# 105358-3SC001-01-B_CPU_BRD.net
KiCad netlist of a schematic drawn in Altium Designer
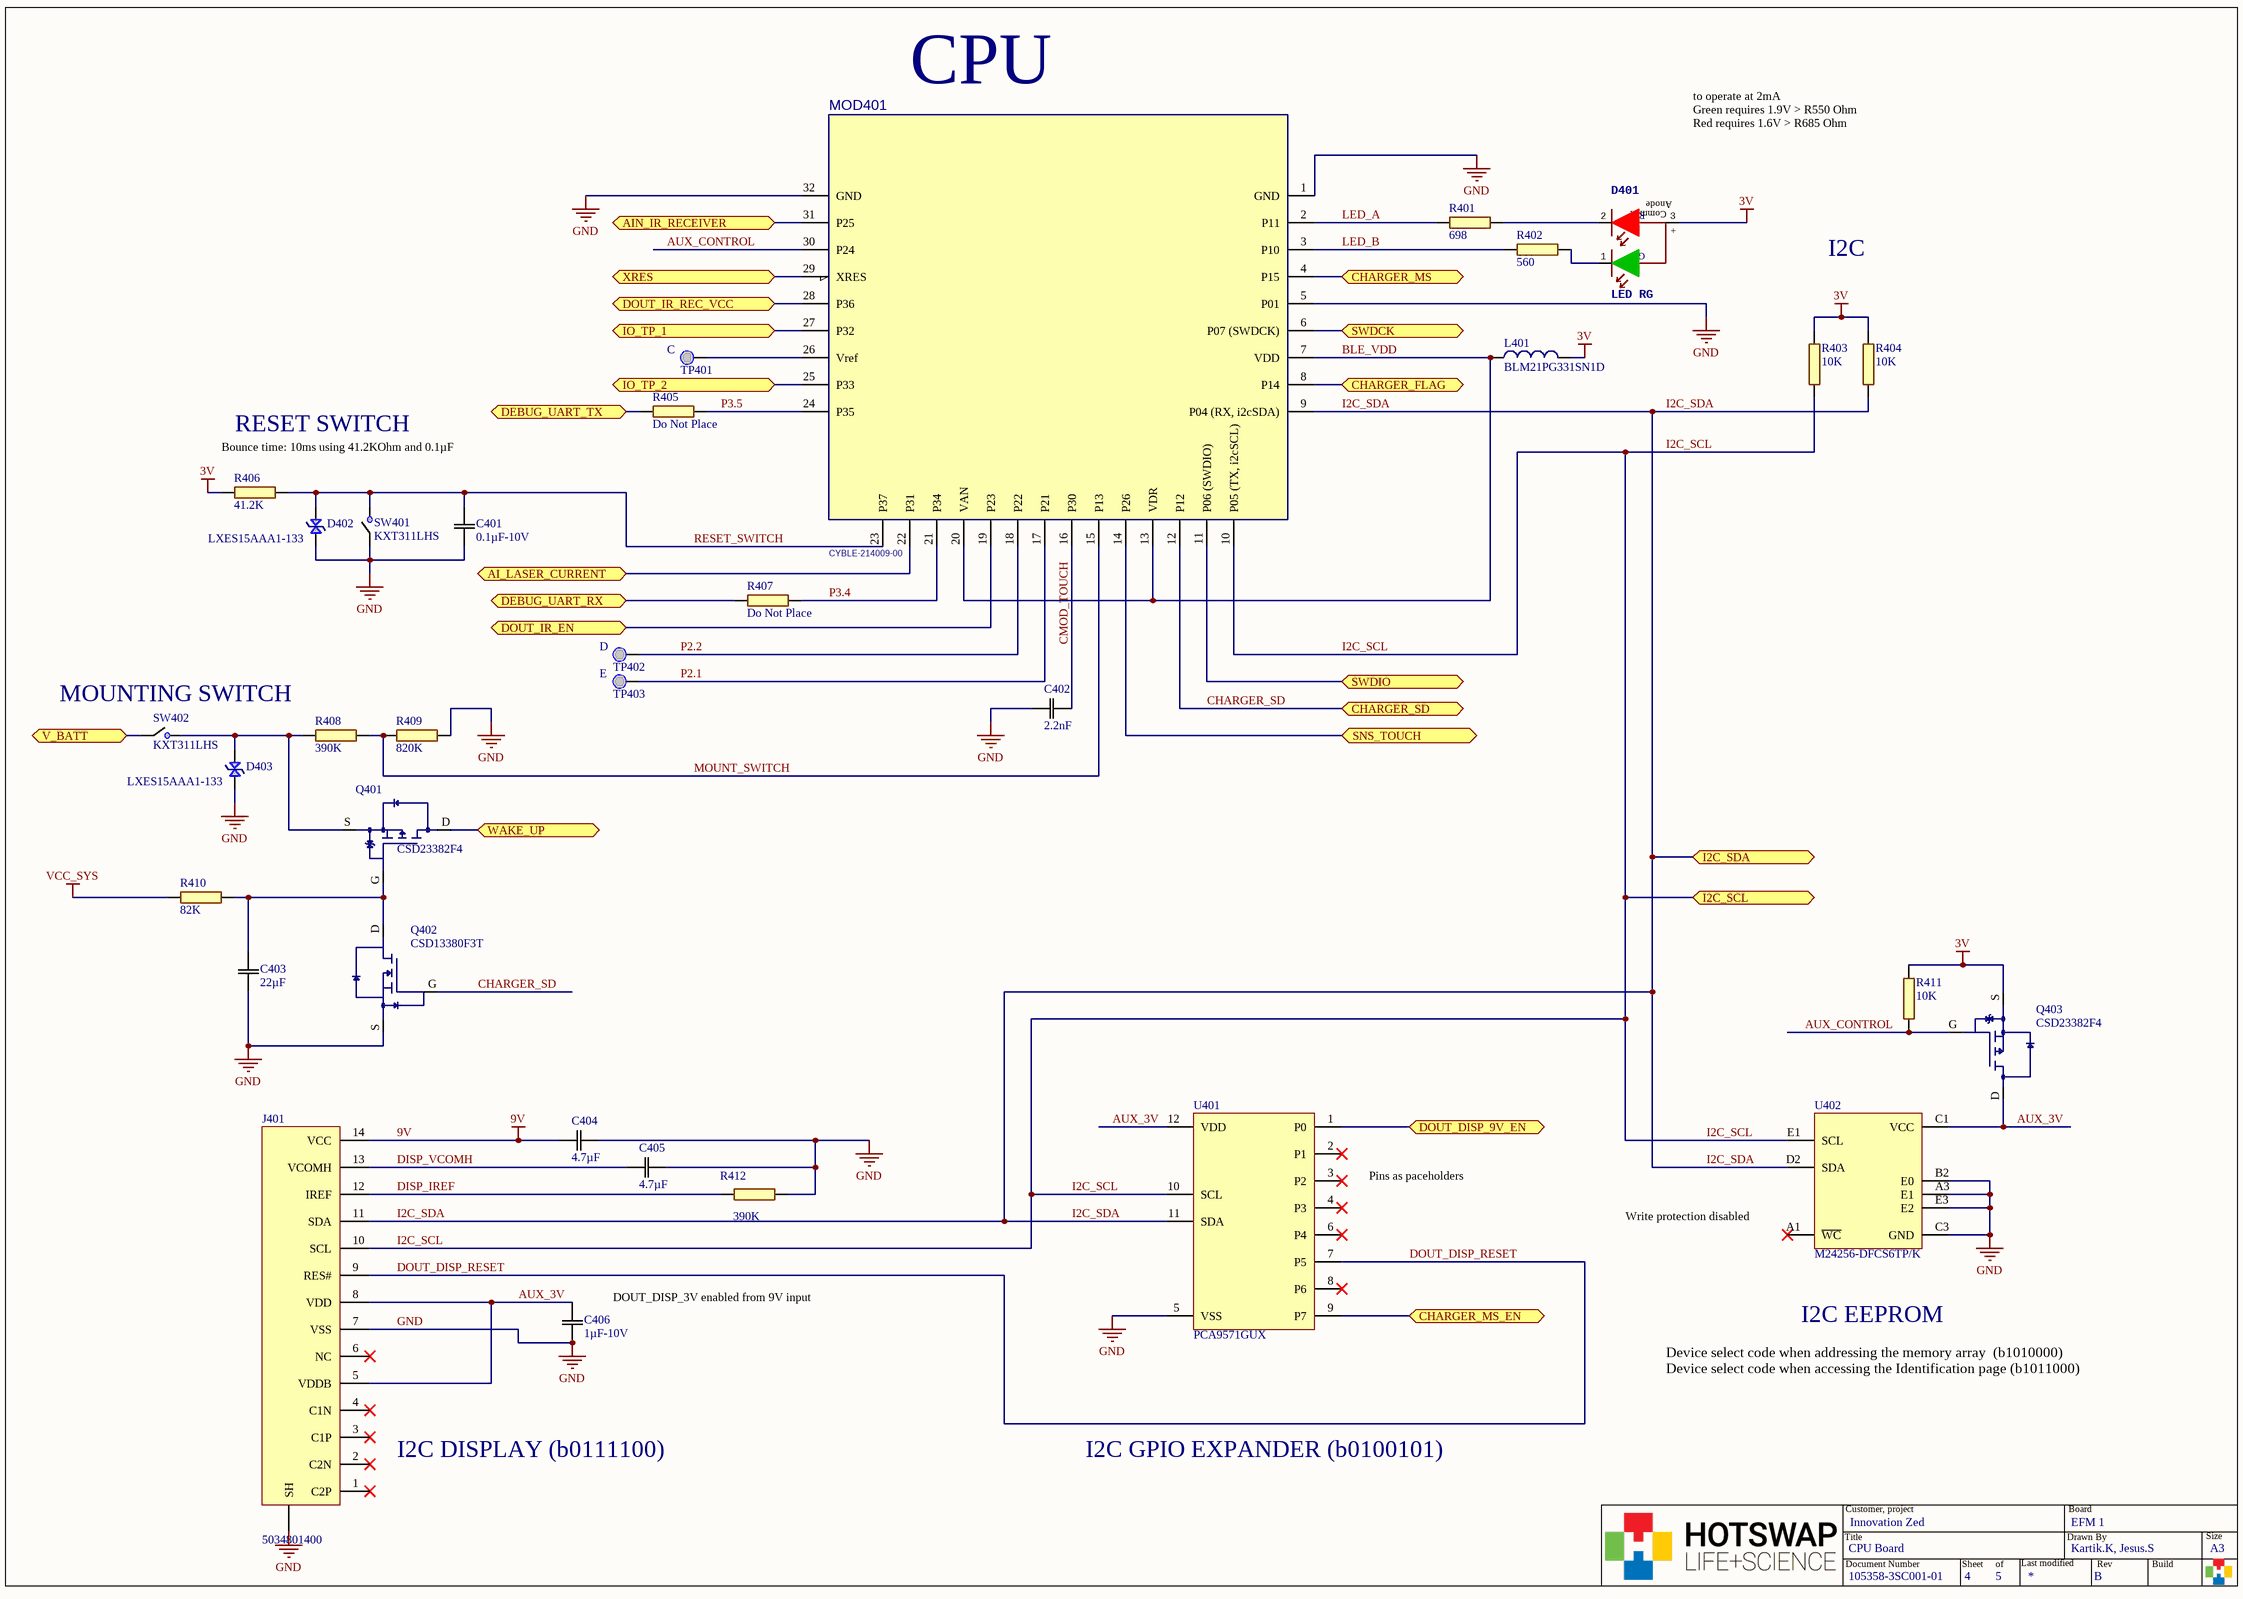
[diagram p0: 105358-3SC001-01-B_CPU_BRD.SchDoc]

(export (version "E")
  (design (tool "Eeschema 10.0.6"))
  (components
    (comp (ref "C401")
      (value "0.1µF-10V")
      (footprint "0402C_HIGH_DENSITY")
      (description "0.1µF ±10% 10V X5R Ceramic Capacitor 0402")
      (fields
        (field (name "MANUFACTURER PART NUMBER") "CC0402KRX5R6BB104")
        (field (name "MANUFACTURER") "Yageo")
      )
      (libsource (lib "ConnectMedical") (part "0402C-0.1uF-10V"))
    )
    (comp (ref "C402")
      (value "2.2nF")
      (footprint "0402C_HIGH_DENSITY")
      (description "2.2nF ±10% 50V X5R Ceramic Capacitor 0402")
      (fields
        (field (name "MANUFACTURER PART NUMBER") "GRM155R61H222KA01D")
        (field (name "MANUFACTURER") "Murata Electronics North America")
      )
      (libsource (lib "ConnectMedical") (part "0402C-2.2nF-50V"))
    )
    (comp (ref "C403")
      (value "22µF")
      (footprint "0603C-GENERIC")
      (description "22µF ±20% 10V Ceramic Capacitor X5R 0603")
      (fields
        (field (name "MANUFACTURER PART NUMBER") "C1608X5R1A226M080AC")
        (field (name "MANUFACTURER") "TDK Corporation")
      )
      (libsource (lib "ConnectMedical") (part "0603C-22uF-10V"))
    )
    (comp (ref "C404")
      (value "4.7µF")
      (footprint "0402C_HIGH_DENSITY")
      (description "4.7µF ±10% 6.3V X5R Ceramic Capacitor 0402")
      (fields
        (field (name "MANUFACTURER PART NUMBER") "C1005X5R0J475K050BC")
        (field (name "MANUFACTURER") "TDK Corporation")
      )
      (libsource (lib "ConnectMedical") (part "0402C-4.7uF-6.3V"))
    )
    (comp (ref "C405")
      (value "4.7µF")
      (footprint "0402C_HIGH_DENSITY")
      (description "4.7µF ±10% 6.3V X5R Ceramic Capacitor 0402")
      (fields
        (field (name "MANUFACTURER PART NUMBER") "C1005X5R0J475K050BC")
        (field (name "MANUFACTURER") "TDK Corporation")
      )
      (libsource (lib "ConnectMedical") (part "0402C-4.7uF-6.3V"))
    )
    (comp (ref "C406")
      (value "1µF-10V")
      (footprint "0402C_HIGH_DENSITY")
      (description "1µF ±10% 10V X5R Ceramic Capacitor 0402")
      (fields
        (field (name "MANUFACTURER PART NUMBER") "CC0402KRX5R6BB105")
        (field (name "MANUFACTURER") "Yageo")
      )
      (libsource (lib "ConnectMedical") (part "0402C-1uF-10V"))
    )
    (comp (ref "D401")
      (value "LED RG")
      (footprint "LED GRN/RED DIFF 1208 R/A SMD")
      (description "LED GRN/RED DIFF 1208 R/A SMD")
      (fields
        (field (name "MANUFACTURER") "Stanley Electric Co")
        (field (name "MANUFACTURER PART NUMBER") "BRPY1211F-TR")
      )
      (libsource (lib "ConnectMedical") (part "LED GRN/RED DIFF 1208 R/A SMD"))
    )
    (comp (ref "D402")
      (value "LXES15AAA1-133")
      (footprint "0402C-GENERIC")
      (description "TVS DIODE 15VWM 0402")
      (fields
        (field (name "MANUFACTURER") "Murata Electronics North America")
        (field (name "DIGI-KEY PART NUMBER") "490-13209-1-ND")
      )
      (libsource (lib "ConnectMedical") (part "TVS DIODE 15VWM 0402"))
    )
    (comp (ref "D403")
      (value "LXES15AAA1-133")
      (footprint "0402C-GENERIC")
      (description "TVS DIODE 15VWM 0402")
      (fields
        (field (name "MANUFACTURER") "Murata Electronics North America")
        (field (name "DIGI-KEY PART NUMBER") "490-13209-1-ND")
      )
      (libsource (lib "ConnectMedical") (part "TVS DIODE 15VWM 0402"))
    )
    (comp (ref "J401")
      (value "5034801400")
      (footprint "5034801400")
      (description "Connector molex to OLED Display")
      (fields (field (name "MANUFACTURER") "Molex, LLC") (field (name "DIGI-KEY PART NUMBER") "WM1442CT-ND"))
      (libsource (lib "ConnectMedical") (part "Molex-5034801400"))
    )
    (comp (ref "L401")
      (value "BLM21PG331SN1D")
      (footprint "0805L_HIGH_DENSITY - Hybrid 0402")
      (description "0805 Ferrite Bead 330Ohm@100MHz")
      (fields
        (field (name "DIGI-KEY PART NUMBER") "490-5988-1-ND")
        (field (name "MANUFACTURER") "Murata Electronics North America")
      )
      (libsource (lib "ConnectMedical") (part "BLM21PG331SN1D"))
    )
    (comp (ref "MOD401")
      (value "CYBLE-214009-00")
      (footprint "CYBLE-014008-00_MinKeepOut")
      (description "BLE PSoC Module 4.1")
      (fields
        (field (name "MANUFACTURER") "Cypress Semiconductor Corp")
        (field (name "DIGI-KEY PART NUMBER") "428-3809-ND")
      )
      (libsource (lib "ConnectMedical") (part "CYBLE-214009-00"))
    )
    (comp (ref "Q401")
      (value "CSD23382F4")
      (footprint "CSD23382F4 -DFN65P100X35-3L")
      (description "MOSFET P-CH 12V 22A 3PICOSTAR")
      (fields
        (field (name "DIGI-KEY PART NUMBER") "296-40003-1-ND")
        (field (name "MANUFACTURER") "Texas Instruments")
      )
      (libsource (lib "ConnectMedical") (part "CSD23382F4"))
    )
    (comp (ref "Q402")
      (value "CSD13380F3T")
      (footprint "CSD13380F3-DFN40P69X35-3L")
      (description "12V N-CHANNEL FEMTOFET MOSFET")
      (fields (field (name "MANUFACTURER") "Texas Instruments"))
      (libsource (lib "ConnectMedical") (part "CSD13380F3T"))
    )
    (comp (ref "Q403")
      (value "CSD23382F4")
      (footprint "CSD23382F4 -DFN65P100X35-3L")
      (description "MOSFET P-CH 12V 22A 3PICOSTAR")
      (fields
        (field (name "DIGI-KEY PART NUMBER") "296-40003-1-ND")
        (field (name "MANUFACTURER") "Texas Instruments")
      )
      (libsource (lib "ConnectMedical") (part "CSD23382F4"))
    )
    (comp (ref "R401")
      (value "698")
      (footprint "0402R-GENERIC")
      (description "RES SMD 698 OHM 1% 1/16W 0402")
      (fields (field (name "DIGI-KEY PART NUMBER") "YAG3215CT-ND") (field (name "MANUFACTURER") "Yageo"))
      (libsource (lib "ConnectMedical") (part "0402R-698 OHM-1%-0.063W"))
    )
    (comp (ref "R402")
      (value "560")
      (footprint "0402R-GENERIC")
      (description "RES SMD 560OHM 1% 1/16W 0402")
      (fields
        (field (name "DIGI-KEY PART NUMBER") "1276-3473-1-ND")
        (field (name "MANUFACTURER") "Samsung Electro-Mechanics America, Inc.")
      )
      (libsource (lib "ConnectMedical") (part "0402R-560 OHM-1%-0.063W"))
    )
    (comp (ref "R403")
      (value "10K")
      (footprint "0402R-GENERIC")
      (description "RES SMD 10kOHM 1% 1/16W 0402")
      (fields (field (name "DIGI-KEY PART NUMBER") "311-10.0KLRCT-ND") (field (name "MANUFACTURER") "Yageo"))
      (libsource (lib "ConnectMedical") (part "0402R-10k OHM-1%-0.063W"))
    )
    (comp (ref "R404")
      (value "10K")
      (footprint "0402R-GENERIC")
      (description "RES SMD 10kOHM 1% 1/16W 0402")
      (fields (field (name "DIGI-KEY PART NUMBER") "311-10.0KLRCT-ND") (field (name "MANUFACTURER") "Yageo"))
      (libsource (lib "ConnectMedical") (part "0402R-10k OHM-1%-0.063W"))
    )
    (comp (ref "R405")
      (value "Do Not Place")
      (footprint "0402R-GENERIC")
      (libsource (lib "ConnectMedical") (part "0402R-Do Not Place"))
    )
    (comp (ref "R406")
      (value "41.2K")
      (footprint "0402R-GENERIC")
      (description "RES SMD 41.2kOHM 1% 1/16W 0402")
      (fields (field (name "DIGI-KEY PART NUMBER") "YAG3155CT-ND") (field (name "MANUFACTURER") "Yageo"))
      (libsource (lib "ConnectMedical") (part "0402R-41.2k OHM-1%-0.063W"))
    )
    (comp (ref "R407")
      (value "Do Not Place")
      (footprint "0402R-GENERIC")
      (libsource (lib "ConnectMedical") (part "0402R-Do Not Place"))
    )
    (comp (ref "R408")
      (value "390K")
      (footprint "0402R-GENERIC")
      (description "RES SMD 390kOHM 1% 1/16W 0402")
      (fields (field (name "DIGI-KEY PART NUMBER") "YAG3143CT-ND") (field (name "MANUFACTURER") "Yageo"))
      (libsource (lib "ConnectMedical") (part "0402R-390k OHM-1%-0.063W"))
    )
    (comp (ref "R409")
      (value "820K")
      (footprint "0402R-GENERIC")
      (description "RES SMD 820kOHM 1% 1/16W 0402")
      (fields (field (name "DIGI-KEY PART NUMBER") "YAG3240CT-ND") (field (name "MANUFACTURER") "Yageo"))
      (libsource (lib "ConnectMedical") (part "0402R-820k OHM-1%-0.063W"))
    )
    (comp (ref "R410")
      (value "82K")
      (footprint "0402R-GENERIC")
      (description "RES SMD 82kOHM 1% 1/16W 0402")
      (fields (field (name "DIGI-KEY PART NUMBER") "311-82.0KLRCT-ND") (field (name "MANUFACTURER") "Yageo"))
      (libsource (lib "ConnectMedical") (part "0402R-82k OHM-1%-0.063W"))
    )
    (comp (ref "R411")
      (value "10K")
      (footprint "0402R-GENERIC")
      (description "RES SMD 10kOHM 1% 1/16W 0402")
      (fields (field (name "DIGI-KEY PART NUMBER") "311-10.0KLRCT-ND") (field (name "MANUFACTURER") "Yageo"))
      (libsource (lib "ConnectMedical") (part "0402R-10k OHM-1%-0.063W"))
    )
    (comp (ref "R412")
      (value "390K")
      (footprint "0402R-GENERIC")
      (description "RES SMD 390kOHM 1% 1/16W 0402")
      (fields (field (name "DIGI-KEY PART NUMBER") "YAG3143CT-ND") (field (name "MANUFACTURER") "Yageo"))
      (libsource (lib "ConnectMedical") (part "0402R-390k OHM-1%-0.063W"))
    )
    (comp (ref "SW401")
      (value "KXT311LHS")
      (footprint "KXT311LHS_B")
      (description "SPST Tactile Switch")
      (fields (field (name "MANUFACTURER PART NUMBER") "KXT 311 LHS") (field (name "MANUFACTURER") "C&K"))
      (libsource (lib "ConnectMedical") (part "KXT311LHS"))
    )
    (comp (ref "SW402")
      (value "KXT311LHS")
      (footprint "KXT311LHS_B")
      (description "SPST Tactile Switch")
      (fields (field (name "MANUFACTURER PART NUMBER") "KXT 311 LHS") (field (name "MANUFACTURER") "C&K"))
      (libsource (lib "ConnectMedical") (part "KXT311LHS"))
    )
    (comp (ref "TP401")
      (value "TEST POINT")
      (footprint "PAD TEST POINT")
      (description "Testing Poiny")
      (libsource (lib "ConnectMedical") (part "TEST POINT"))
    )
    (comp (ref "TP402")
      (value "TEST POINT")
      (footprint "PAD TEST POINT")
      (description "Testing Poiny")
      (libsource (lib "ConnectMedical") (part "TEST POINT"))
    )
    (comp (ref "TP403")
      (value "TEST POINT")
      (footprint "PAD TEST POINT")
      (description "Testing Poiny")
      (libsource (lib "ConnectMedical") (part "TEST POINT"))
    )
    (comp (ref "U401")
      (value "PCA9571GUX")
      (footprint "PCA9571-XQFN12")
      (description "IC I/O EXPANDER I2C 12XQFN")
      (fields
        (field (name "MANUFACTURER") "NXP USA Inc.")
        (field (name "DIGI-KEY PART NUMBER") "568-12400-1-ND")
      )
      (libsource (lib "ConnectMedical") (part "PCA9571GUX"))
    )
    (comp (ref "U402")
      (value "M24256-DFCS6TP/K")
      (footprint "BGAS8_M24256-DFCS6_1")
      (description "IC EEPROM 256KBIT 1MHZ 8WLCSP")
      (fields
        (field (name "MANUFACTURER") "STMicroelectronics")
        (field (name "DIGI-KEY PART NUMBER") "497-13611-1-ND")
      )
      (libsource (lib "ConnectMedical") (part "M24256-DFCS6TPK"))
    )
  )
  (nets
    (net (code "1") (name "/AIN_IR_RECEIVER") (class "Default")
      (node (ref "MOD401") (pin "31") (pinfunction "P25_31") (pintype "passive"))
    )
    (net (code "2") (name "/AI_LASER_CURRENT") (class "Default")
      (node (ref "MOD401") (pin "22") (pinfunction "P31_22") (pintype "passive"))
    )
    (net (code "3") (name "/AUX_3V") (class "Default")
      (node (ref "C406") (pin "2") (pinfunction "2_2") (pintype "passive"))
      (node (ref "J401") (pin "5") (pinfunction "VDDB_5") (pintype "passive"))
      (node (ref "J401") (pin "8") (pinfunction "VDD_8") (pintype "passive"))
      (node (ref "Q403") (pin "D") (pinfunction "3_D") (pintype "passive"))
      (node (ref "U401") (pin "12") (pinfunction "VDD_12") (pintype "passive"))
      (node (ref "U402") (pin "C1") (pinfunction "VCC_C1") (pintype "passive"))
    )
    (net (code "4") (name "/AUX_CONTROL") (class "Default")
      (node (ref "MOD401") (pin "30") (pinfunction "P24_30") (pintype "passive"))
      (node (ref "Q403") (pin "G") (pinfunction "1_G") (pintype "passive"))
      (node (ref "R411") (pin "2") (pintype "passive"))
    )
    (net (code "5") (name "/BLE_VDD") (class "Default")
      (node (ref "L401") (pin "1") (pinfunction "1_1") (pintype "passive"))
      (node (ref "MOD401") (pin "13") (pinfunction "VDR_13") (pintype "power_in"))
      (node (ref "MOD401") (pin "20") (pinfunction "VAN_20") (pintype "power_in"))
      (node (ref "MOD401") (pin "7") (pinfunction "VDD_7") (pintype "power_in"))
    )
    (net (code "6") (name "/CHARGER_FLAG") (class "Default")
      (node (ref "MOD401") (pin "8") (pinfunction "P14_8") (pintype "passive"))
    )
    (net (code "7") (name "/CHARGER_MS") (class "Default")
      (node (ref "MOD401") (pin "4") (pinfunction "P15_4") (pintype "passive"))
    )
    (net (code "8") (name "/CHARGER_MS_EN") (class "Default")
      (node (ref "U401") (pin "9") (pinfunction "P7_9") (pintype "passive"))
    )
    (net (code "9") (name "/CHARGER_SD") (class "Default")
      (node (ref "MOD401") (pin "12") (pinfunction "P12_12") (pintype "passive"))
      (node (ref "Q402") (pin "G") (pinfunction "1_G") (pintype "passive"))
    )
    (net (code "10") (name "/CMOD_TOUCH") (class "Default")
      (node (ref "C402") (pin "1") (pinfunction "1_1") (pintype "passive"))
      (node (ref "MOD401") (pin "16") (pinfunction "P30_16") (pintype "passive"))
    )
    (net (code "11") (name "/DEBUG_UART_RX") (class "Default")
      (node (ref "R407") (pin "1") (pintype "passive"))
    )
    (net (code "12") (name "/DEBUG_UART_TX") (class "Default")
      (node (ref "R405") (pin "1") (pintype "passive"))
    )
    (net (code "13") (name "/DISP_IREF") (class "Default")
      (node (ref "J401") (pin "12") (pinfunction "IREF_12") (pintype "passive"))
      (node (ref "R412") (pin "1") (pintype "passive"))
    )
    (net (code "14") (name "/DISP_VCOMH") (class "Default")
      (node (ref "C405") (pin "2") (pinfunction "2_2") (pintype "passive"))
      (node (ref "J401") (pin "13") (pinfunction "VCOMH_13") (pintype "passive"))
    )
    (net (code "15") (name "/DOUT_DISP_9V_EN") (class "Default")
      (node (ref "U401") (pin "1") (pinfunction "P0_1") (pintype "passive"))
    )
    (net (code "16") (name "/DOUT_DISP_RESET") (class "Default")
      (node (ref "J401") (pin "9") (pinfunction "RES#_9") (pintype "passive"))
      (node (ref "U401") (pin "7") (pinfunction "P5_7") (pintype "passive"))
    )
    (net (code "17") (name "/DOUT_IR_EN") (class "Default")
      (node (ref "MOD401") (pin "19") (pinfunction "P23_19") (pintype "passive"))
    )
    (net (code "18") (name "/DOUT_IR_REC_VCC") (class "Default")
      (node (ref "MOD401") (pin "28") (pinfunction "P36_28") (pintype "passive"))
    )
    (net (code "19") (name "/I2C_SCL") (class "Default")
      (node (ref "J401") (pin "10") (pinfunction "SCL_10") (pintype "passive"))
      (node (ref "MOD401") (pin "10") (pinfunction "P05_(TX,_i2cSCL)_10") (pintype "passive"))
      (node (ref "R403") (pin "2") (pintype "passive"))
      (node (ref "U401") (pin "10") (pinfunction "SCL_10") (pintype "passive"))
      (node (ref "U402") (pin "E1") (pinfunction "SCL_E1") (pintype "passive"))
    )
    (net (code "20") (name "/I2C_SDA") (class "Default")
      (node (ref "J401") (pin "11") (pinfunction "SDA_11") (pintype "passive"))
      (node (ref "MOD401") (pin "9") (pinfunction "P04_(RX,_i2cSDA)_9") (pintype "passive"))
      (node (ref "R404") (pin "2") (pintype "passive"))
      (node (ref "U401") (pin "11") (pinfunction "SDA_11") (pintype "passive"))
      (node (ref "U402") (pin "D2") (pinfunction "SDA_D2") (pintype "passive"))
    )
    (net (code "21") (name "/IO_TP_1") (class "Default")
      (node (ref "MOD401") (pin "27") (pinfunction "P32_27") (pintype "passive"))
    )
    (net (code "22") (name "/IO_TP_2") (class "Default")
      (node (ref "MOD401") (pin "25") (pinfunction "P33_25") (pintype "passive"))
    )
    (net (code "23") (name "/LED_A") (class "Default")
      (node (ref "MOD401") (pin "2") (pinfunction "P11_2") (pintype "passive"))
      (node (ref "R401") (pin "1") (pintype "passive"))
    )
    (net (code "24") (name "/LED_B") (class "Default")
      (node (ref "MOD401") (pin "3") (pinfunction "P10_3") (pintype "passive"))
      (node (ref "R402") (pin "1") (pintype "passive"))
    )
    (net (code "25") (name "/MOUNT_SWITCH") (class "Default")
      (node (ref "MOD401") (pin "15") (pinfunction "P13_15") (pintype "passive"))
      (node (ref "R408") (pin "2") (pintype "passive"))
      (node (ref "R409") (pin "2") (pintype "passive"))
    )
    (net (code "26") (name "/P2.1") (class "Default")
      (node (ref "MOD401") (pin "17") (pinfunction "P21_17") (pintype "passive"))
      (node (ref "TP403") (pin "1") (pinfunction "Test_Point_1") (pintype "passive"))
    )
    (net (code "27") (name "/P2.2") (class "Default")
      (node (ref "MOD401") (pin "18") (pinfunction "P22_18") (pintype "passive"))
      (node (ref "TP402") (pin "1") (pinfunction "Test_Point_1") (pintype "passive"))
    )
    (net (code "28") (name "/P3.4") (class "Default")
      (node (ref "MOD401") (pin "21") (pinfunction "P34_21") (pintype "passive"))
      (node (ref "R407") (pin "2") (pintype "passive"))
    )
    (net (code "29") (name "/P3.5") (class "Default")
      (node (ref "MOD401") (pin "24") (pinfunction "P35_24") (pintype "passive"))
      (node (ref "R405") (pin "2") (pintype "passive"))
    )
    (net (code "30") (name "/RESET_SWITCH") (class "Default")
      (node (ref "C401") (pin "2") (pinfunction "2_2") (pintype "passive"))
      (node (ref "D402") (pin "2") (pinfunction "2_2") (pintype "passive"))
      (node (ref "MOD401") (pin "23") (pinfunction "P37_23") (pintype "passive"))
      (node (ref "R406") (pin "2") (pintype "passive"))
      (node (ref "SW401") (pin "2") (pinfunction "2_2") (pintype "passive"))
    )
    (net (code "31") (name "/SNS_TOUCH") (class "Default")
      (node (ref "MOD401") (pin "14") (pinfunction "P26_14") (pintype "passive"))
    )
    (net (code "32") (name "/SWDCK") (class "Default")
      (node (ref "MOD401") (pin "6") (pinfunction "P07_(SWDCK)_6") (pintype "passive"))
    )
    (net (code "33") (name "/SWDIO") (class "Default")
      (node (ref "MOD401") (pin "11") (pinfunction "P06_(SWDIO)_11") (pintype "passive"))
    )
    (net (code "34") (name "/V_BATT") (class "Default")
      (node (ref "SW402") (pin "1") (pinfunction "1_1") (pintype "passive"))
    )
    (net (code "35") (name "/WAKE_UP") (class "Default")
      (node (ref "Q401") (pin "D") (pinfunction "3_D") (pintype "passive"))
    )
    (net (code "36") (name "/XRES") (class "Default")
      (node (ref "MOD401") (pin "29") (pinfunction "XRES_29") (pintype "passive"))
    )
    (net (code "37") (name "3V") (class "Default")
      (node (ref "D401") (pin "3") (pinfunction "3_3") (pintype "passive"))
      (node (ref "L401") (pin "2") (pinfunction "2_2") (pintype "passive"))
      (node (ref "Q403") (pin "S") (pinfunction "2_S") (pintype "passive"))
      (node (ref "R403") (pin "1") (pintype "passive"))
      (node (ref "R404") (pin "1") (pintype "passive"))
      (node (ref "R406") (pin "1") (pintype "passive"))
      (node (ref "R411") (pin "1") (pintype "passive"))
    )
    (net (code "38") (name "9V") (class "Default")
      (node (ref "C404") (pin "1") (pinfunction "1_1") (pintype "passive"))
      (node (ref "J401") (pin "14") (pinfunction "VCC_14") (pintype "passive"))
    )
    (net (code "39") (name "GND") (class "Default")
      (node (ref "C401") (pin "1") (pinfunction "1_1") (pintype "passive"))
      (node (ref "C402") (pin "2") (pinfunction "2_2") (pintype "passive"))
      (node (ref "C403") (pin "1") (pinfunction "1_1") (pintype "passive"))
      (node (ref "C404") (pin "2") (pinfunction "2_2") (pintype "passive"))
      (node (ref "C405") (pin "1") (pinfunction "1_1") (pintype "passive"))
      (node (ref "C406") (pin "1") (pinfunction "1_1") (pintype "passive"))
      (node (ref "D402") (pin "1") (pinfunction "1_1") (pintype "passive"))
      (node (ref "D403") (pin "1") (pinfunction "1_1") (pintype "passive"))
      (node (ref "J401") (pin "7") (pinfunction "VSS_7") (pintype "power_in"))
      (node (ref "J401") (pin "SH") (pinfunction "SH_SH") (pintype "passive"))
      (node (ref "MOD401") (pin "1") (pinfunction "GND_1") (pintype "power_in"))
      (node (ref "MOD401") (pin "32") (pinfunction "GND_32") (pintype "power_in"))
      (node (ref "MOD401") (pin "5") (pinfunction "P01_5") (pintype "passive"))
      (node (ref "Q402") (pin "S") (pinfunction "2_S") (pintype "passive"))
      (node (ref "R409") (pin "1") (pintype "passive"))
      (node (ref "R412") (pin "2") (pintype "passive"))
      (node (ref "SW401") (pin "1") (pinfunction "1_1") (pintype "passive"))
      (node (ref "U401") (pin "5") (pinfunction "VSS_5") (pintype "passive"))
      (node (ref "U402") (pin "A3") (pinfunction "E1_A3") (pintype "passive"))
      (node (ref "U402") (pin "B2") (pinfunction "E0_B2") (pintype "passive"))
      (node (ref "U402") (pin "C3") (pinfunction "GND_C3") (pintype "passive"))
      (node (ref "U402") (pin "E3") (pinfunction "E2_E3") (pintype "passive"))
    )
    (net (code "40") (name "Net-(D401-G)") (class "Default")
      (node (ref "D401") (pin "2") (pinfunction "G_2") (pintype "passive"))
      (node (ref "R401") (pin "2") (pintype "passive"))
    )
    (net (code "41") (name "Net-(D401-R)") (class "Default")
      (node (ref "D401") (pin "1") (pinfunction "R_1") (pintype "passive"))
      (node (ref "R402") (pin "2") (pintype "passive"))
    )
    (net (code "42") (name "Net-(MOD401-Vref)") (class "Default")
      (node (ref "MOD401") (pin "26") (pinfunction "Vref_26") (pintype "power_in"))
      (node (ref "TP401") (pin "1") (pinfunction "Test_Point_1") (pintype "passive"))
    )
    (net (code "43") (name "Net-(Q401-1)") (class "Default")
      (node (ref "C403") (pin "2") (pinfunction "2_2") (pintype "passive"))
      (node (ref "Q401") (pin "G") (pinfunction "1_G") (pintype "passive"))
      (node (ref "Q402") (pin "D") (pinfunction "3_D") (pintype "passive"))
      (node (ref "R410") (pin "2") (pintype "passive"))
    )
    (net (code "44") (name "Net-(Q401-2)") (class "Default")
      (node (ref "D403") (pin "2") (pinfunction "2_2") (pintype "passive"))
      (node (ref "Q401") (pin "S") (pinfunction "2_S") (pintype "passive"))
      (node (ref "R408") (pin "1") (pintype "passive"))
      (node (ref "SW402") (pin "2") (pinfunction "2_2") (pintype "passive"))
    )
    (net (code "45") (name "VCC_SYS") (class "Default") (node (ref "R410") (pin "1") (pintype "passive")))
    (net (code "46") (name "unconnected-(J401-C1N-Pad4)") (class "Default")
      (node (ref "J401") (pin "4") (pinfunction "C1N_4") (pintype "passive+no_connect"))
    )
    (net (code "47") (name "unconnected-(J401-C1P-Pad3)") (class "Default")
      (node (ref "J401") (pin "3") (pinfunction "C1P_3") (pintype "passive+no_connect"))
    )
    (net (code "48") (name "unconnected-(J401-C2N-Pad2)") (class "Default")
      (node (ref "J401") (pin "2") (pinfunction "C2N_2") (pintype "passive+no_connect"))
    )
    (net (code "49") (name "unconnected-(J401-C2P-Pad1)") (class "Default")
      (node (ref "J401") (pin "1") (pinfunction "C2P_1") (pintype "passive+no_connect"))
    )
    (net (code "50") (name "unconnected-(J401-NC-Pad6)") (class "Default")
      (node (ref "J401") (pin "6") (pinfunction "NC_6") (pintype "passive+no_connect"))
    )
    (net (code "51") (name "unconnected-(U401-P1-Pad2)") (class "Default")
      (node (ref "U401") (pin "2") (pinfunction "P1_2") (pintype "passive+no_connect"))
    )
    (net (code "52") (name "unconnected-(U401-P2-Pad3)") (class "Default")
      (node (ref "U401") (pin "3") (pinfunction "P2_3") (pintype "passive+no_connect"))
    )
    (net (code "53") (name "unconnected-(U401-P3-Pad4)") (class "Default")
      (node (ref "U401") (pin "4") (pinfunction "P3_4") (pintype "passive+no_connect"))
    )
    (net (code "54") (name "unconnected-(U401-P4-Pad6)") (class "Default")
      (node (ref "U401") (pin "6") (pinfunction "P4_6") (pintype "passive+no_connect"))
    )
    (net (code "55") (name "unconnected-(U401-P6-Pad8)") (class "Default")
      (node (ref "U401") (pin "8") (pinfunction "P6_8") (pintype "passive+no_connect"))
    )
    (net (code "56") (name "unconnected-(U402-~{WC}-PadA1)") (class "Default")
      (node (ref "U402") (pin "A1") (pinfunction "~{WC}_A1") (pintype "passive+no_connect"))
    )
  )
)
